# UART_to_USB.net
KiCad netlist of a schematic drawn in Altium Designer
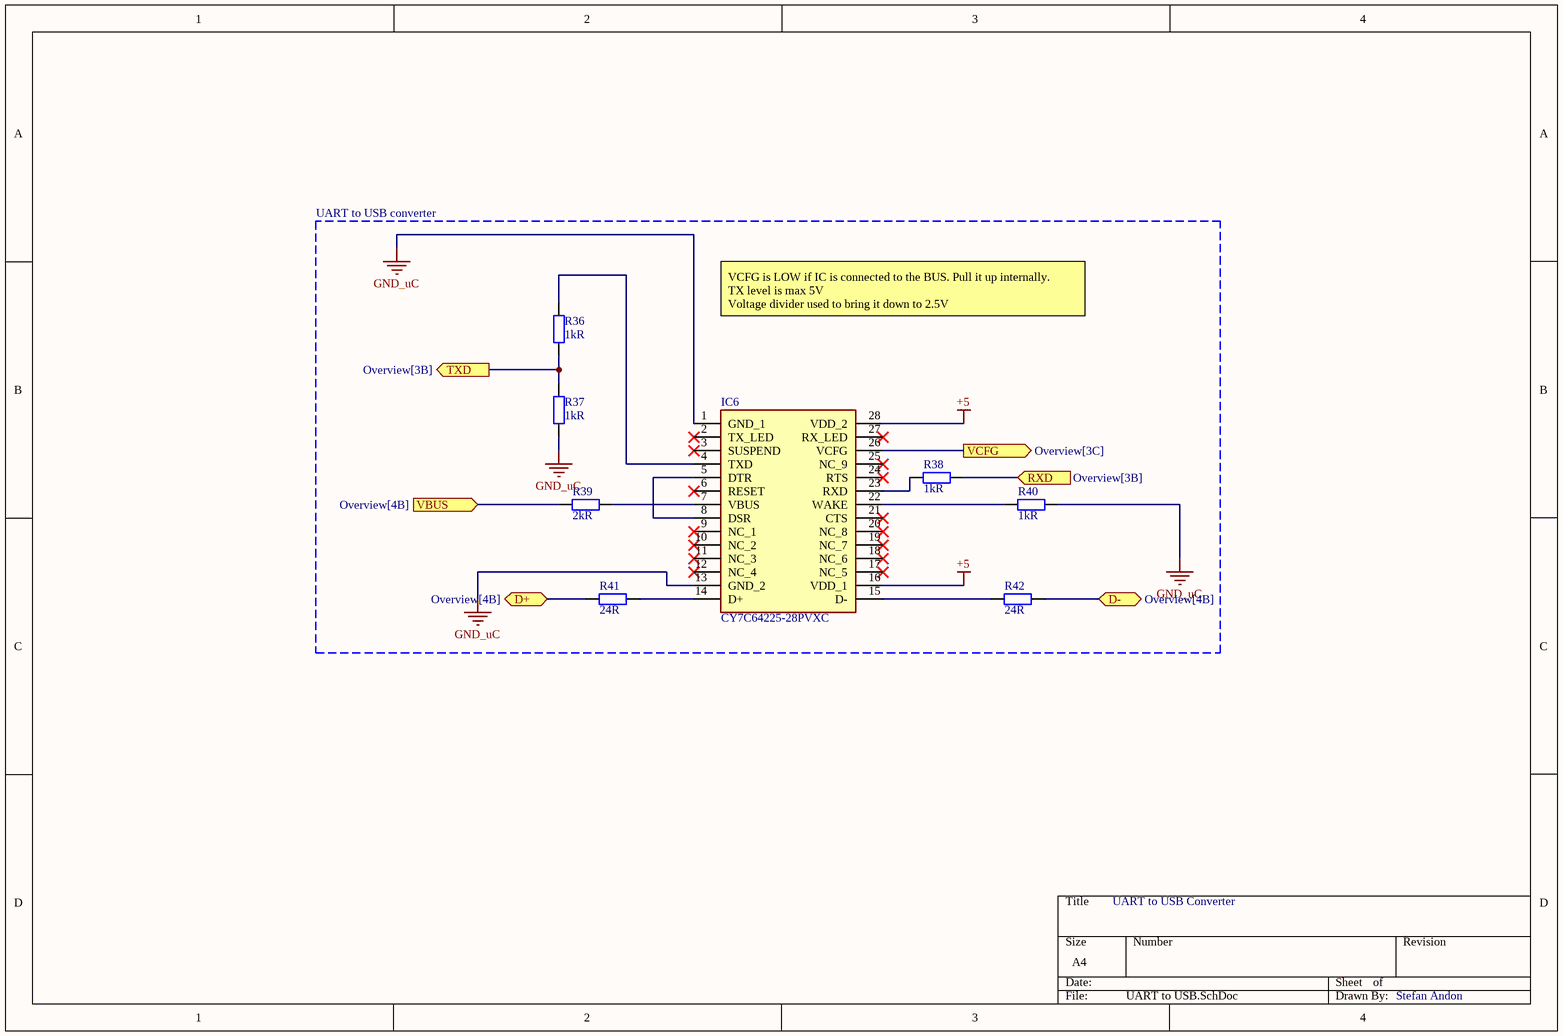
[diagram p0: UART to USB.SchDoc]

(export (version "E")
  (design (tool "Eeschema 10.0.6"))
  (components
    (comp (ref "IC6")
      (value "CY7C64225-28PVXC")
      (footprint "SamacSys:SOP65P780X200-28N")
      (description "Integrated Circuit")
      (fields (field (name "MOUSER PART NUMBER") "727-CY7C64225-28PVXC"))
      (libsource (lib "*") (part "CY7C64225-28PVXC"))
    )
    (comp (ref "R36")
      (value "1kR")
      (footprint "RES_0603")
      (fields
        (field (name "TOLERANCE") "tbd")
        (field (name "POWER") "7W")
        (field (name "Comment") "Resistor_SMD")
      )
      (libsource (lib "") (part "Resistor_1"))
    )
    (comp (ref "R37")
      (value "1kR")
      (footprint "RES_0603")
      (fields
        (field (name "TOLERANCE") "tbd")
        (field (name "POWER") "7W")
        (field (name "Comment") "Resistor_SMD")
      )
      (libsource (lib "") (part "Resistor_1"))
    )
    (comp (ref "R38")
      (value "1kR")
      (footprint "RES_0603")
      (fields
        (field (name "TOLERANCE") "tbd")
        (field (name "POWER") "7W")
        (field (name "Comment") "Resistor_SMD")
      )
      (libsource (lib "") (part "Resistor_2"))
    )
    (comp (ref "R39")
      (value "2kR")
      (footprint "RES_0603")
      (fields
        (field (name "TOLERANCE") "tbd")
        (field (name "POWER") "7W")
        (field (name "Comment") "Resistor_SMD")
      )
      (libsource (lib "TUfast e") (part "Resistor"))
    )
    (comp (ref "R40")
      (value "1kR")
      (footprint "RES_0603")
      (fields
        (field (name "TOLERANCE") "tbd")
        (field (name "POWER") "7W")
        (field (name "Comment") "Resistor_SMD")
      )
      (libsource (lib "TUfast e") (part "Resistor"))
    )
    (comp (ref "R41")
      (value "24R")
      (footprint "RES_0603")
      (fields
        (field (name "TOLERANCE") "tbd")
        (field (name "POWER") "7W")
        (field (name "Comment") "Resistor_SMD")
      )
      (libsource (lib "TUfast e") (part "Resistor"))
    )
    (comp (ref "R42")
      (value "24R")
      (footprint "RES_0603")
      (fields
        (field (name "TOLERANCE") "tbd")
        (field (name "POWER") "7W")
        (field (name "Comment") "Resistor_SMD")
      )
      (libsource (lib "TUfast e") (part "Resistor"))
    )
  )
  (nets
    (net (code "1") (name "+5") (class "Default")
      (node (ref "IC6") (pin "16") (pinfunction "VDD_1_16") (pintype "passive"))
      (node (ref "IC6") (pin "28") (pinfunction "VDD_2_28") (pintype "passive"))
    )
    (net (code "2") (name "/D+") (class "Default")
      (node (ref "R41") (pin "1") (pinfunction "1_1") (pintype "passive"))
    )
    (net (code "3") (name "/D-") (class "Default")
      (node (ref "R42") (pin "2") (pinfunction "2_2") (pintype "passive"))
    )
    (net (code "4") (name "/RXD") (class "Default")
      (node (ref "R38") (pin "1") (pinfunction "1_1") (pintype "passive"))
    )
    (net (code "5") (name "/TXD") (class "Default")
      (node (ref "R36") (pin "1") (pinfunction "1_1") (pintype "passive"))
      (node (ref "R37") (pin "2") (pinfunction "2_2") (pintype "passive"))
    )
    (net (code "6") (name "/VBUS") (class "Default")
      (node (ref "R39") (pin "1") (pinfunction "1_1") (pintype "passive"))
    )
    (net (code "7") (name "/VCFG") (class "Default")
      (node (ref "IC6") (pin "26") (pinfunction "VCFG_26") (pintype "passive"))
    )
    (net (code "8") (name "GND_uC") (class "Default")
      (node (ref "IC6") (pin "1") (pinfunction "GND_1_1") (pintype "passive"))
      (node (ref "IC6") (pin "13") (pinfunction "GND_2_13") (pintype "passive"))
      (node (ref "R37") (pin "1") (pinfunction "1_1") (pintype "passive"))
      (node (ref "R40") (pin "2") (pinfunction "2_2") (pintype "passive"))
    )
    (net (code "9") (name "Net-(IC6-D+)") (class "Default")
      (node (ref "IC6") (pin "14") (pinfunction "D+_14") (pintype "passive"))
      (node (ref "R41") (pin "2") (pinfunction "2_2") (pintype "passive"))
    )
    (net (code "10") (name "Net-(IC6-D-)") (class "Default")
      (node (ref "IC6") (pin "15") (pinfunction "D-_15") (pintype "passive"))
      (node (ref "R42") (pin "1") (pinfunction "1_1") (pintype "passive"))
    )
    (net (code "11") (name "Net-(IC6-DSR)") (class "Default")
      (node (ref "IC6") (pin "5") (pinfunction "DTR_5") (pintype "passive"))
      (node (ref "IC6") (pin "8") (pinfunction "DSR_8") (pintype "passive"))
    )
    (net (code "12") (name "Net-(IC6-RXD)") (class "Default")
      (node (ref "IC6") (pin "23") (pinfunction "RXD_23") (pintype "passive"))
      (node (ref "R38") (pin "2") (pinfunction "2_2") (pintype "passive"))
    )
    (net (code "13") (name "Net-(IC6-TXD)") (class "Default")
      (node (ref "IC6") (pin "4") (pinfunction "TXD_4") (pintype "passive"))
      (node (ref "R36") (pin "2") (pinfunction "2_2") (pintype "passive"))
    )
    (net (code "14") (name "Net-(IC6-VBUS)") (class "Default")
      (node (ref "IC6") (pin "7") (pinfunction "VBUS_7") (pintype "passive"))
      (node (ref "R39") (pin "2") (pinfunction "2_2") (pintype "passive"))
    )
    (net (code "15") (name "Net-(IC6-WAKE)") (class "Default")
      (node (ref "IC6") (pin "22") (pinfunction "WAKE_22") (pintype "passive"))
      (node (ref "R40") (pin "1") (pinfunction "1_1") (pintype "passive"))
    )
    (net (code "16") (name "unconnected-(IC6-CTS-Pad21)") (class "Default")
      (node (ref "IC6") (pin "21") (pinfunction "CTS_21") (pintype "passive+no_connect"))
    )
    (net (code "17") (name "unconnected-(IC6-NC_1-Pad9)") (class "Default")
      (node (ref "IC6") (pin "9") (pinfunction "NC_1_9") (pintype "passive+no_connect"))
    )
    (net (code "18") (name "unconnected-(IC6-NC_2-Pad10)") (class "Default")
      (node (ref "IC6") (pin "10") (pinfunction "NC_2_10") (pintype "passive+no_connect"))
    )
    (net (code "19") (name "unconnected-(IC6-NC_3-Pad11)") (class "Default")
      (node (ref "IC6") (pin "11") (pinfunction "NC_3_11") (pintype "passive+no_connect"))
    )
    (net (code "20") (name "unconnected-(IC6-NC_4-Pad12)") (class "Default")
      (node (ref "IC6") (pin "12") (pinfunction "NC_4_12") (pintype "passive+no_connect"))
    )
    (net (code "21") (name "unconnected-(IC6-NC_5-Pad17)") (class "Default")
      (node (ref "IC6") (pin "17") (pinfunction "NC_5_17") (pintype "passive+no_connect"))
    )
    (net (code "22") (name "unconnected-(IC6-NC_6-Pad18)") (class "Default")
      (node (ref "IC6") (pin "18") (pinfunction "NC_6_18") (pintype "passive+no_connect"))
    )
    (net (code "23") (name "unconnected-(IC6-NC_7-Pad19)") (class "Default")
      (node (ref "IC6") (pin "19") (pinfunction "NC_7_19") (pintype "passive+no_connect"))
    )
    (net (code "24") (name "unconnected-(IC6-NC_8-Pad20)") (class "Default")
      (node (ref "IC6") (pin "20") (pinfunction "NC_8_20") (pintype "passive+no_connect"))
    )
    (net (code "25") (name "unconnected-(IC6-NC_9-Pad25)") (class "Default")
      (node (ref "IC6") (pin "25") (pinfunction "NC_9_25") (pintype "passive+no_connect"))
    )
    (net (code "26") (name "unconnected-(IC6-RESET-Pad6)") (class "Default")
      (node (ref "IC6") (pin "6") (pinfunction "RESET_6") (pintype "passive+no_connect"))
    )
    (net (code "27") (name "unconnected-(IC6-RTS-Pad24)") (class "Default")
      (node (ref "IC6") (pin "24") (pinfunction "RTS_24") (pintype "passive+no_connect"))
    )
    (net (code "28") (name "unconnected-(IC6-RX_LED-Pad27)") (class "Default")
      (node (ref "IC6") (pin "27") (pinfunction "RX_LED_27") (pintype "passive+no_connect"))
    )
    (net (code "29") (name "unconnected-(IC6-SUSPEND-Pad3)") (class "Default")
      (node (ref "IC6") (pin "3") (pinfunction "SUSPEND_3") (pintype "passive+no_connect"))
    )
    (net (code "30") (name "unconnected-(IC6-TX_LED-Pad2)") (class "Default")
      (node (ref "IC6") (pin "2") (pinfunction "TX_LED_2") (pintype "passive+no_connect"))
    )
  )
)
